# harvester_hat.net
KiCad netlist of a schematic drawn in EAGLE
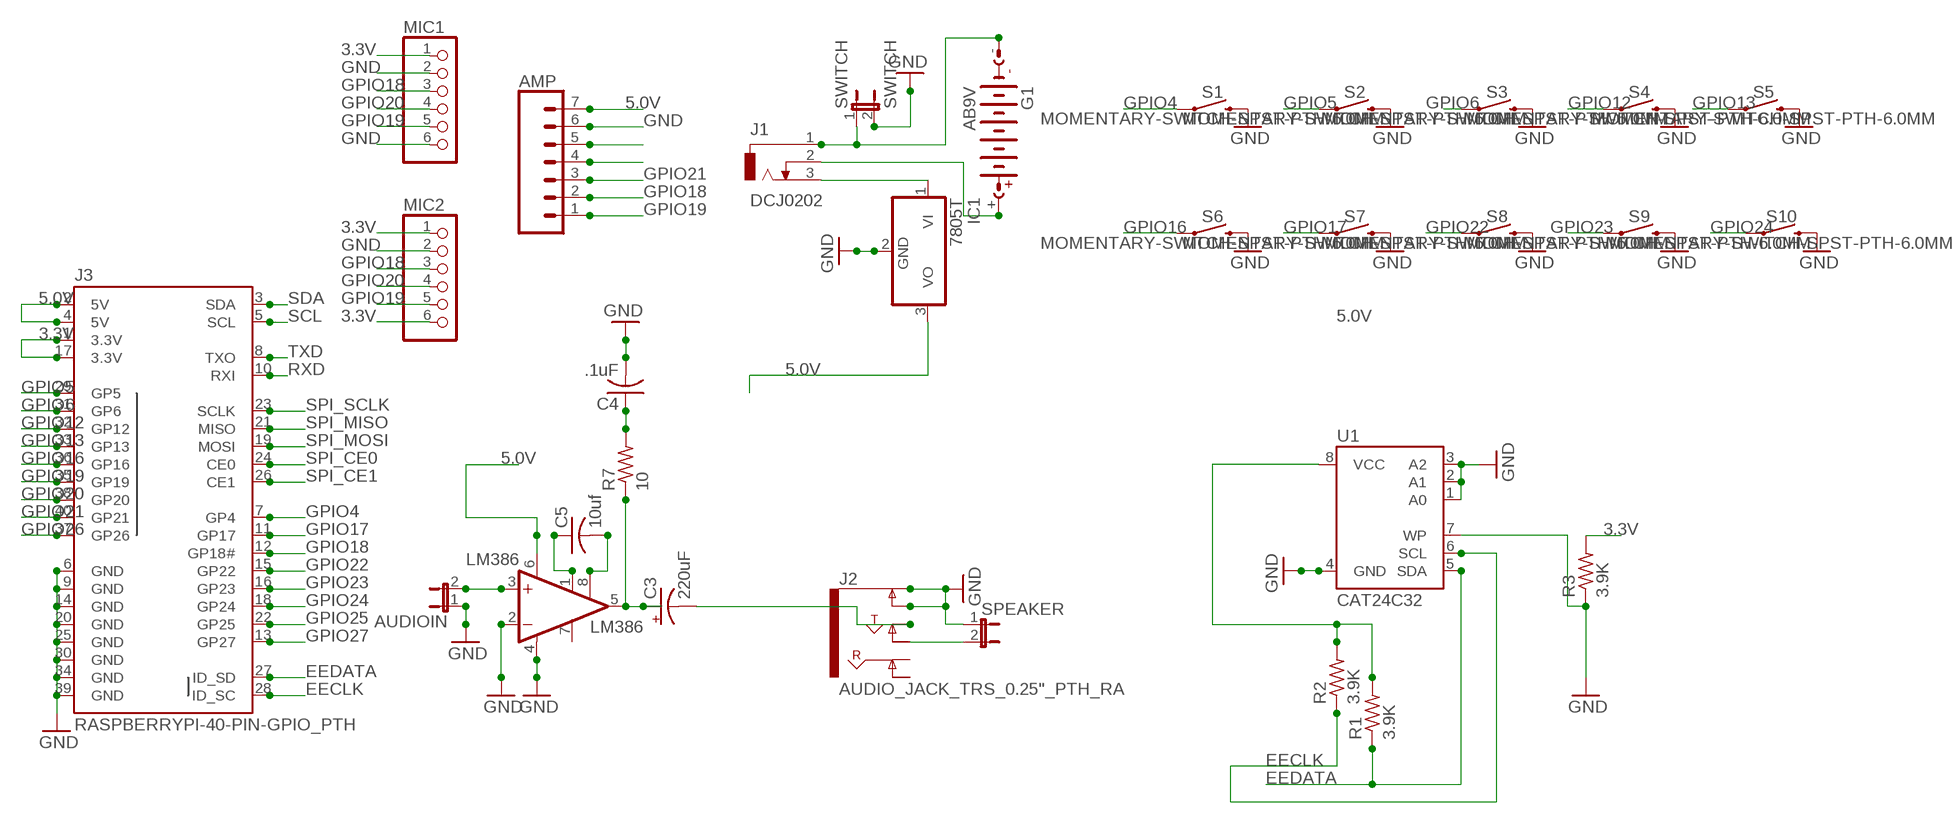
[diagram p0: schematic, sheet 1]

(export (version "E")
  (design (tool "Eeschema 10.0.6"))
  (components
    (comp (ref "AMP")
      (value "CONN_07")
      (footprint "eagle-import:1X07")
      (libsource (lib "eagle-import") (part "CONN_07"))
    )
    (comp (ref "AUDIOIN")
      (value "JP1E")
      (footprint "eagle-import:JP1")
      (libsource (lib "eagle-import") (part "JP1E"))
    )
    (comp (ref "C3")
      (value "220uF")
      (footprint "eagle-import:E3,5-8")
      (libsource (lib "eagle-import") (part "CPOL-USE3.5-8"))
    )
    (comp (ref "C4")
      (value ".1uF")
      (footprint "eagle-import:C025-024X044")
      (libsource (lib "eagle-import") (part "C-US025-024X044"))
    )
    (comp (ref "C5")
      (value "10uf")
      (footprint "eagle-import:C025-024X044")
      (libsource (lib "eagle-import") (part "C-US025-024X044"))
    )
    (comp (ref "G1")
      (value "AB9V")
      (footprint "eagle-import:AB9V")
      (libsource (lib "eagle-import") (part "AB9V"))
    )
    (comp (ref "IC1")
      (value "7805T")
      (footprint "eagle-import:TO220H")
      (libsource (lib "eagle-import") (part "78T05"))
    )
    (comp (ref "J1")
      (value "DCJ0202")
      (footprint "eagle-import:DCJ0202")
      (libsource (lib "eagle-import") (part "DCJ0202"))
    )
    (comp (ref "J2")
      (value "AUDIO_JACK_TRS_0.25\"_PTH_RA")
      (footprint "eagle-import:AUDIO_JACK_0.25__TRS_PTH_RA")
      (libsource (lib "eagle-import") (part "AUDIO_JACK_TRS_0.25{dblquote}_PTH_RA"))
    )
    (comp (ref "J3")
      (value "RASPBERRYPI-40-PIN-GPIO_PTH")
      (footprint "eagle-import:2X20_SHROUDED")
      (libsource (lib "eagle-import") (part "RASPBERRYPI-40-PIN-GPIO_PTH"))
    )
    (comp (ref "LM386")
      (value "LM386")
      (footprint "eagle-import:DIL08")
      (libsource (lib "eagle-import") (part "LM386?-N1"))
    )
    (comp (ref "MIC1")
      (value "PINHD-1X6")
      (footprint "eagle-import:1X06")
      (libsource (lib "eagle-import") (part "PINHD-1X6"))
    )
    (comp (ref "MIC2")
      (value "PINHD-1X6")
      (footprint "eagle-import:1X06")
      (libsource (lib "eagle-import") (part "PINHD-1X6"))
    )
    (comp (ref "R1")
      (value "3.9K")
      (footprint "eagle-import:0207_10")
      (libsource (lib "eagle-import") (part "resistor_348_R-US_0207/10"))
    )
    (comp (ref "R2")
      (value "3.9K")
      (footprint "eagle-import:0207_10")
      (libsource (lib "eagle-import") (part "resistor_348_R-US_0207/10"))
    )
    (comp (ref "R3")
      (value "3.9K")
      (footprint "eagle-import:0207_10")
      (libsource (lib "eagle-import") (part "resistor_348_R-US_0207/10"))
    )
    (comp (ref "R7")
      (value "10")
      (footprint "eagle-import:0204_7")
      (libsource (lib "eagle-import") (part "R-US_0204/7"))
    )
    (comp (ref "S1")
      (value "MOMENTARY-SWITCH-SPST-PTH-6.0MM")
      (footprint "eagle-import:TACTILE_SWITCH_PTH_6.0MM")
      (libsource (lib "eagle-import") (part "MOMENTARY-SWITCH-SPST-PTH-6.0MM"))
    )
    (comp (ref "S2")
      (value "MOMENTARY-SWITCH-SPST-PTH-6.0MM")
      (footprint "eagle-import:TACTILE_SWITCH_PTH_6.0MM")
      (libsource (lib "eagle-import") (part "MOMENTARY-SWITCH-SPST-PTH-6.0MM"))
    )
    (comp (ref "S3")
      (value "MOMENTARY-SWITCH-SPST-PTH-6.0MM")
      (footprint "eagle-import:TACTILE_SWITCH_PTH_6.0MM")
      (libsource (lib "eagle-import") (part "MOMENTARY-SWITCH-SPST-PTH-6.0MM"))
    )
    (comp (ref "S4")
      (value "MOMENTARY-SWITCH-SPST-PTH-6.0MM")
      (footprint "eagle-import:TACTILE_SWITCH_PTH_6.0MM")
      (libsource (lib "eagle-import") (part "MOMENTARY-SWITCH-SPST-PTH-6.0MM"))
    )
    (comp (ref "S5")
      (value "MOMENTARY-SWITCH-SPST-PTH-6.0MM")
      (footprint "eagle-import:TACTILE_SWITCH_PTH_6.0MM")
      (libsource (lib "eagle-import") (part "MOMENTARY-SWITCH-SPST-PTH-6.0MM"))
    )
    (comp (ref "S6")
      (value "MOMENTARY-SWITCH-SPST-PTH-6.0MM")
      (footprint "eagle-import:TACTILE_SWITCH_PTH_6.0MM")
      (libsource (lib "eagle-import") (part "MOMENTARY-SWITCH-SPST-PTH-6.0MM"))
    )
    (comp (ref "S7")
      (value "MOMENTARY-SWITCH-SPST-PTH-6.0MM")
      (footprint "eagle-import:TACTILE_SWITCH_PTH_6.0MM")
      (libsource (lib "eagle-import") (part "MOMENTARY-SWITCH-SPST-PTH-6.0MM"))
    )
    (comp (ref "S8")
      (value "MOMENTARY-SWITCH-SPST-PTH-6.0MM")
      (footprint "eagle-import:TACTILE_SWITCH_PTH_6.0MM")
      (libsource (lib "eagle-import") (part "MOMENTARY-SWITCH-SPST-PTH-6.0MM"))
    )
    (comp (ref "S9")
      (value "MOMENTARY-SWITCH-SPST-PTH-6.0MM")
      (footprint "eagle-import:TACTILE_SWITCH_PTH_6.0MM")
      (libsource (lib "eagle-import") (part "MOMENTARY-SWITCH-SPST-PTH-6.0MM"))
    )
    (comp (ref "S10")
      (value "MOMENTARY-SWITCH-SPST-PTH-6.0MM")
      (footprint "eagle-import:TACTILE_SWITCH_PTH_6.0MM")
      (libsource (lib "eagle-import") (part "MOMENTARY-SWITCH-SPST-PTH-6.0MM"))
    )
    (comp (ref "SPEAKER")
      (value "JP1E")
      (footprint "eagle-import:JP1")
      (libsource (lib "eagle-import") (part "JP1E"))
    )
    (comp (ref "SWITCH")
      (value "SWITCH")
      (footprint "eagle-import:JP1")
      (libsource (lib "eagle-import") (part "JP1E"))
    )
    (comp (ref "U1")
      (value "CAT24C32")
      (footprint "eagle-import:DIL08")
      (fields (field (name "MPN") "AT24C1024BW-SH-B"))
      (libsource (lib "eagle-import") (part "AT24CP"))
    )
  )
  (nets
    (net (code "1") (name "/3.3V") (class "Default")
      (node (ref "J3") (pin "1") (pinfunction "3.3V_1") (pintype "power_in"))
      (node (ref "J3") (pin "17") (pinfunction "3.3V_17") (pintype "power_in"))
      (node (ref "MIC1") (pin "1") (pinfunction "1_1") (pintype "passive"))
      (node (ref "MIC2") (pin "1") (pinfunction "1_1") (pintype "passive"))
      (node (ref "MIC2") (pin "6") (pinfunction "6_6") (pintype "passive"))
      (node (ref "R3") (pin "2") (pinfunction "2_2") (pintype "passive"))
    )
    (net (code "2") (name "/5.0V") (class "Default")
      (node (ref "AMP") (pin "7") (pinfunction "7_7") (pintype "passive"))
      (node (ref "IC1") (pin "3") (pinfunction "VO_3") (pintype "passive"))
      (node (ref "J3") (pin "2") (pinfunction "5V_2") (pintype "power_in"))
      (node (ref "J3") (pin "4") (pinfunction "5V_4") (pintype "power_in"))
      (node (ref "LM386") (pin "6") (pinfunction "VS_6") (pintype "power_in"))
      (node (ref "R1") (pin "2") (pinfunction "2_2") (pintype "passive"))
      (node (ref "R2") (pin "2") (pinfunction "2_2") (pintype "passive"))
      (node (ref "U1") (pin "8") (pinfunction "VCC_8") (pintype "power_in"))
    )
    (net (code "3") (name "/EECLK") (class "Default")
      (node (ref "J3") (pin "28") (pinfunction "ID_SC_28") (pintype "bidirectional"))
      (node (ref "R2") (pin "1") (pinfunction "1_1") (pintype "passive"))
      (node (ref "U1") (pin "6") (pinfunction "SCL_6") (pintype "bidirectional"))
    )
    (net (code "4") (name "/EEDATA") (class "Default")
      (node (ref "J3") (pin "27") (pinfunction "ID_SD_27") (pintype "bidirectional"))
      (node (ref "R1") (pin "1") (pinfunction "1_1") (pintype "passive"))
      (node (ref "U1") (pin "5") (pinfunction "SDA_5") (pintype "bidirectional"))
    )
    (net (code "5") (name "/GPIO4") (class "Default")
      (node (ref "J3") (pin "7") (pinfunction "GP4_7") (pintype "bidirectional"))
      (node (ref "S1") (pin "1") (pinfunction "1_1") (pintype "passive"))
    )
    (net (code "6") (name "/GPIO5") (class "Default")
      (node (ref "J3") (pin "29") (pinfunction "GP5_29") (pintype "bidirectional"))
      (node (ref "S2") (pin "1") (pinfunction "1_1") (pintype "passive"))
    )
    (net (code "7") (name "/GPIO6") (class "Default")
      (node (ref "J3") (pin "31") (pinfunction "GP6_31") (pintype "bidirectional"))
      (node (ref "S3") (pin "1") (pinfunction "1_1") (pintype "passive"))
    )
    (net (code "8") (name "/GPIO12") (class "Default")
      (node (ref "J3") (pin "32") (pinfunction "GP12_32") (pintype "bidirectional"))
      (node (ref "S4") (pin "1") (pinfunction "1_1") (pintype "passive"))
    )
    (net (code "9") (name "/GPIO13") (class "Default")
      (node (ref "J3") (pin "33") (pinfunction "GP13_33") (pintype "bidirectional"))
      (node (ref "S5") (pin "1") (pinfunction "1_1") (pintype "passive"))
    )
    (net (code "10") (name "/GPIO16") (class "Default")
      (node (ref "J3") (pin "36") (pinfunction "GP16_36") (pintype "bidirectional"))
      (node (ref "S6") (pin "1") (pinfunction "1_1") (pintype "passive"))
    )
    (net (code "11") (name "/GPIO17") (class "Default")
      (node (ref "J3") (pin "11") (pinfunction "GP17_11") (pintype "bidirectional"))
      (node (ref "S7") (pin "1") (pinfunction "1_1") (pintype "passive"))
    )
    (net (code "12") (name "/GPIO18") (class "Default")
      (node (ref "AMP") (pin "2") (pinfunction "2_2") (pintype "passive"))
      (node (ref "J3") (pin "12") (pinfunction "GP18#_12") (pintype "bidirectional"))
      (node (ref "MIC1") (pin "3") (pinfunction "3_3") (pintype "passive"))
      (node (ref "MIC2") (pin "3") (pinfunction "3_3") (pintype "passive"))
    )
    (net (code "13") (name "/GPIO19") (class "Default")
      (node (ref "AMP") (pin "1") (pinfunction "1_1") (pintype "passive"))
      (node (ref "J3") (pin "35") (pinfunction "GP19_35") (pintype "bidirectional"))
      (node (ref "MIC1") (pin "5") (pinfunction "5_5") (pintype "passive"))
      (node (ref "MIC2") (pin "5") (pinfunction "5_5") (pintype "passive"))
    )
    (net (code "14") (name "/GPIO20") (class "Default")
      (node (ref "J3") (pin "38") (pinfunction "GP20_38") (pintype "bidirectional"))
      (node (ref "MIC1") (pin "4") (pinfunction "4_4") (pintype "passive"))
      (node (ref "MIC2") (pin "4") (pinfunction "4_4") (pintype "passive"))
    )
    (net (code "15") (name "/GPIO21") (class "Default")
      (node (ref "AMP") (pin "3") (pinfunction "3_3") (pintype "passive"))
      (node (ref "J3") (pin "40") (pinfunction "GP21_40") (pintype "bidirectional"))
    )
    (net (code "16") (name "/GPIO22") (class "Default")
      (node (ref "J3") (pin "15") (pinfunction "GP22_15") (pintype "bidirectional"))
      (node (ref "S8") (pin "1") (pinfunction "1_1") (pintype "passive"))
    )
    (net (code "17") (name "/GPIO23") (class "Default")
      (node (ref "J3") (pin "16") (pinfunction "GP23_16") (pintype "bidirectional"))
      (node (ref "S9") (pin "1") (pinfunction "1_1") (pintype "passive"))
    )
    (net (code "18") (name "/GPIO24") (class "Default")
      (node (ref "J3") (pin "18") (pinfunction "GP24_18") (pintype "bidirectional"))
      (node (ref "S10") (pin "1") (pinfunction "1_1") (pintype "passive"))
    )
    (net (code "19") (name "/GPIO25") (class "Default")
      (node (ref "J3") (pin "22") (pinfunction "GP25_22") (pintype "bidirectional"))
    )
    (net (code "20") (name "/GPIO26") (class "Default")
      (node (ref "J3") (pin "37") (pinfunction "GP26_37") (pintype "bidirectional"))
    )
    (net (code "21") (name "/GPIO27") (class "Default")
      (node (ref "J3") (pin "13") (pinfunction "GP27_13") (pintype "bidirectional"))
    )
    (net (code "22") (name "/RXD") (class "Default")
      (node (ref "J3") (pin "10") (pinfunction "RXI_10") (pintype "input"))
    )
    (net (code "23") (name "/SCL") (class "Default")
      (node (ref "J3") (pin "5") (pinfunction "SCL_5") (pintype "bidirectional"))
    )
    (net (code "24") (name "/SDA") (class "Default")
      (node (ref "J3") (pin "3") (pinfunction "SDA_3") (pintype "bidirectional"))
    )
    (net (code "25") (name "/SPI_CE0") (class "Default")
      (node (ref "J3") (pin "24") (pinfunction "CE0_24") (pintype "output"))
    )
    (net (code "26") (name "/SPI_CE1") (class "Default")
      (node (ref "J3") (pin "26") (pinfunction "CE1_26") (pintype "output"))
    )
    (net (code "27") (name "/SPI_MISO") (class "Default")
      (node (ref "J3") (pin "21") (pinfunction "MISO_21") (pintype "input"))
    )
    (net (code "28") (name "/SPI_MOSI") (class "Default")
      (node (ref "J3") (pin "19") (pinfunction "MOSI_19") (pintype "output"))
    )
    (net (code "29") (name "/SPI_SCLK") (class "Default")
      (node (ref "J3") (pin "23") (pinfunction "SCLK_23") (pintype "output"))
    )
    (net (code "30") (name "/TXD") (class "Default")
      (node (ref "J3") (pin "8") (pinfunction "TXO_8") (pintype "output"))
    )
    (net (code "31") (name "GND") (class "Default")
      (node (ref "AMP") (pin "6") (pinfunction "6_6") (pintype "passive"))
      (node (ref "AUDIOIN") (pin "1") (pinfunction "1_1") (pintype "passive"))
      (node (ref "C4") (pin "2") (pinfunction "2_2") (pintype "passive"))
      (node (ref "IC1") (pin "2") (pinfunction "GND_2") (pintype "passive"))
      (node (ref "J2") (pin "SLEEVE") (pinfunction "EARTH_SLEEVE") (pintype "bidirectional"))
      (node (ref "J2") (pin "SLEEVE-NORM") (pinfunction "EARTH-NORM_SLEEVE-NORM") (pintype "bidirectional"))
      (node (ref "J3") (pin "14") (pinfunction "GND_14") (pintype "power_in"))
      (node (ref "J3") (pin "20") (pinfunction "GND_20") (pintype "power_in"))
      (node (ref "J3") (pin "25") (pinfunction "GND_25") (pintype "power_in"))
      (node (ref "J3") (pin "30") (pinfunction "GND_30") (pintype "power_in"))
      (node (ref "J3") (pin "34") (pinfunction "GND_34") (pintype "power_in"))
      (node (ref "J3") (pin "39") (pinfunction "GND_39") (pintype "power_in"))
      (node (ref "J3") (pin "6") (pinfunction "GND_6") (pintype "power_in"))
      (node (ref "J3") (pin "9") (pinfunction "GND_9") (pintype "power_in"))
      (node (ref "LM386") (pin "2") (pinfunction "-IN_2") (pintype "input"))
      (node (ref "LM386") (pin "4") (pinfunction "GND_4") (pintype "power_in"))
      (node (ref "MIC1") (pin "2") (pinfunction "2_2") (pintype "passive"))
      (node (ref "MIC1") (pin "6") (pinfunction "6_6") (pintype "passive"))
      (node (ref "MIC2") (pin "2") (pinfunction "2_2") (pintype "passive"))
      (node (ref "R3") (pin "1") (pinfunction "1_1") (pintype "passive"))
      (node (ref "S1") (pin "3") (pinfunction "2_3") (pintype "passive"))
      (node (ref "S10") (pin "3") (pinfunction "2_3") (pintype "passive"))
      (node (ref "S2") (pin "3") (pinfunction "2_3") (pintype "passive"))
      (node (ref "S3") (pin "3") (pinfunction "2_3") (pintype "passive"))
      (node (ref "S4") (pin "3") (pinfunction "2_3") (pintype "passive"))
      (node (ref "S5") (pin "3") (pinfunction "2_3") (pintype "passive"))
      (node (ref "S6") (pin "3") (pinfunction "2_3") (pintype "passive"))
      (node (ref "S7") (pin "3") (pinfunction "2_3") (pintype "passive"))
      (node (ref "S8") (pin "3") (pinfunction "2_3") (pintype "passive"))
      (node (ref "S9") (pin "3") (pinfunction "2_3") (pintype "passive"))
      (node (ref "SPEAKER") (pin "1") (pinfunction "1_1") (pintype "passive"))
      (node (ref "SWITCH") (pin "2") (pinfunction "2_2") (pintype "passive"))
      (node (ref "U1") (pin "1") (pinfunction "A0_1") (pintype "input"))
      (node (ref "U1") (pin "2") (pinfunction "A1_2") (pintype "input"))
      (node (ref "U1") (pin "3") (pinfunction "A2_3") (pintype "input"))
      (node (ref "U1") (pin "4") (pinfunction "GND_4") (pintype "power_in"))
      (node (ref "U1") (pin "7") (pinfunction "WP_7") (pintype "input"))
    )
    (net (code "32") (name "Net-(C3-Pad-)") (class "Default")
      (node (ref "C3") (pin "-") (pinfunction "-_-") (pintype "passive"))
      (node (ref "J2") (pin "TIP") (pinfunction "TIP_TIP") (pintype "bidirectional"))
    )
    (net (code "33") (name "Net-(C4-Pad1)") (class "Default")
      (node (ref "C4") (pin "1") (pinfunction "1_1") (pintype "passive"))
      (node (ref "R7") (pin "2") (pinfunction "2_2") (pintype "passive"))
    )
    (net (code "34") (name "Net-(C5-Pad1)") (class "Default")
      (node (ref "C5") (pin "1") (pinfunction "1_1") (pintype "passive"))
      (node (ref "LM386") (pin "1") (pinfunction "GAIN_1") (pintype "passive"))
    )
    (net (code "35") (name "Net-(C5-Pad2)") (class "Default")
      (node (ref "C5") (pin "2") (pinfunction "2_2") (pintype "passive"))
      (node (ref "LM386") (pin "8") (pinfunction "GAIN_8") (pintype "passive"))
    )
    (net (code "36") (name "Net-(G1-Pad+)") (class "Default")
      (node (ref "G1") (pin "+") (pinfunction "+_+") (pintype "passive"))
      (node (ref "J1") (pin "2") (pinfunction "2_2") (pintype "passive"))
    )
    (net (code "37") (name "Net-(G1-Pad-)") (class "Default")
      (node (ref "G1") (pin "-") (pinfunction "-_-") (pintype "passive"))
      (node (ref "J1") (pin "1") (pinfunction "1_1") (pintype "passive"))
      (node (ref "SWITCH") (pin "1") (pinfunction "1_1") (pintype "passive"))
    )
    (net (code "38") (name "Net-(IC1-VI)") (class "Default")
      (node (ref "IC1") (pin "1") (pinfunction "VI_1") (pintype "input"))
      (node (ref "J1") (pin "3") (pinfunction "3_3") (pintype "passive"))
    )
    (net (code "39") (name "Net-(J2-PadTIP-NORM)") (class "Default")
      (node (ref "J2") (pin "TIP-NORM") (pinfunction "TIP-NORM_TIP-NORM") (pintype "bidirectional"))
      (node (ref "SPEAKER") (pin "2") (pinfunction "2_2") (pintype "passive"))
    )
    (net (code "40") (name "Net-(LM386-+IN)") (class "Default")
      (node (ref "AUDIOIN") (pin "2") (pinfunction "2_2") (pintype "passive"))
      (node (ref "LM386") (pin "3") (pinfunction "+IN_3") (pintype "input"))
    )
    (net (code "41") (name "Net-(LM386-OUT)") (class "Default")
      (node (ref "C3") (pin "+") (pinfunction "+_+") (pintype "passive"))
      (node (ref "LM386") (pin "5") (pinfunction "OUT_5") (pintype "output"))
      (node (ref "R7") (pin "1") (pinfunction "1_1") (pintype "passive"))
    )
    (net (code "42") (name "unconnected-(AMP-Pad4)") (class "Default")
      (node (ref "AMP") (pin "4") (pinfunction "4_4") (pintype "passive"))
    )
    (net (code "43") (name "unconnected-(AMP-Pad5)") (class "Default")
      (node (ref "AMP") (pin "5") (pinfunction "5_5") (pintype "passive"))
    )
    (net (code "44") (name "unconnected-(J2-PadRING)") (class "Default")
      (node (ref "J2") (pin "RING") (pinfunction "RING_RING") (pintype "bidirectional"))
    )
    (net (code "45") (name "unconnected-(J2-PadRING-NORM)") (class "Default")
      (node (ref "J2") (pin "RING-NORM") (pinfunction "RING-NORM_RING-NORM") (pintype "bidirectional"))
    )
    (net (code "46") (name "unconnected-(LM386-BYPASS-Pad7)") (class "Default")
      (node (ref "LM386") (pin "7") (pinfunction "BYPASS_7") (pintype "passive"))
    )
  )
)
